# power_management.net
KiCad netlist of a schematic drawn in Altium Designer
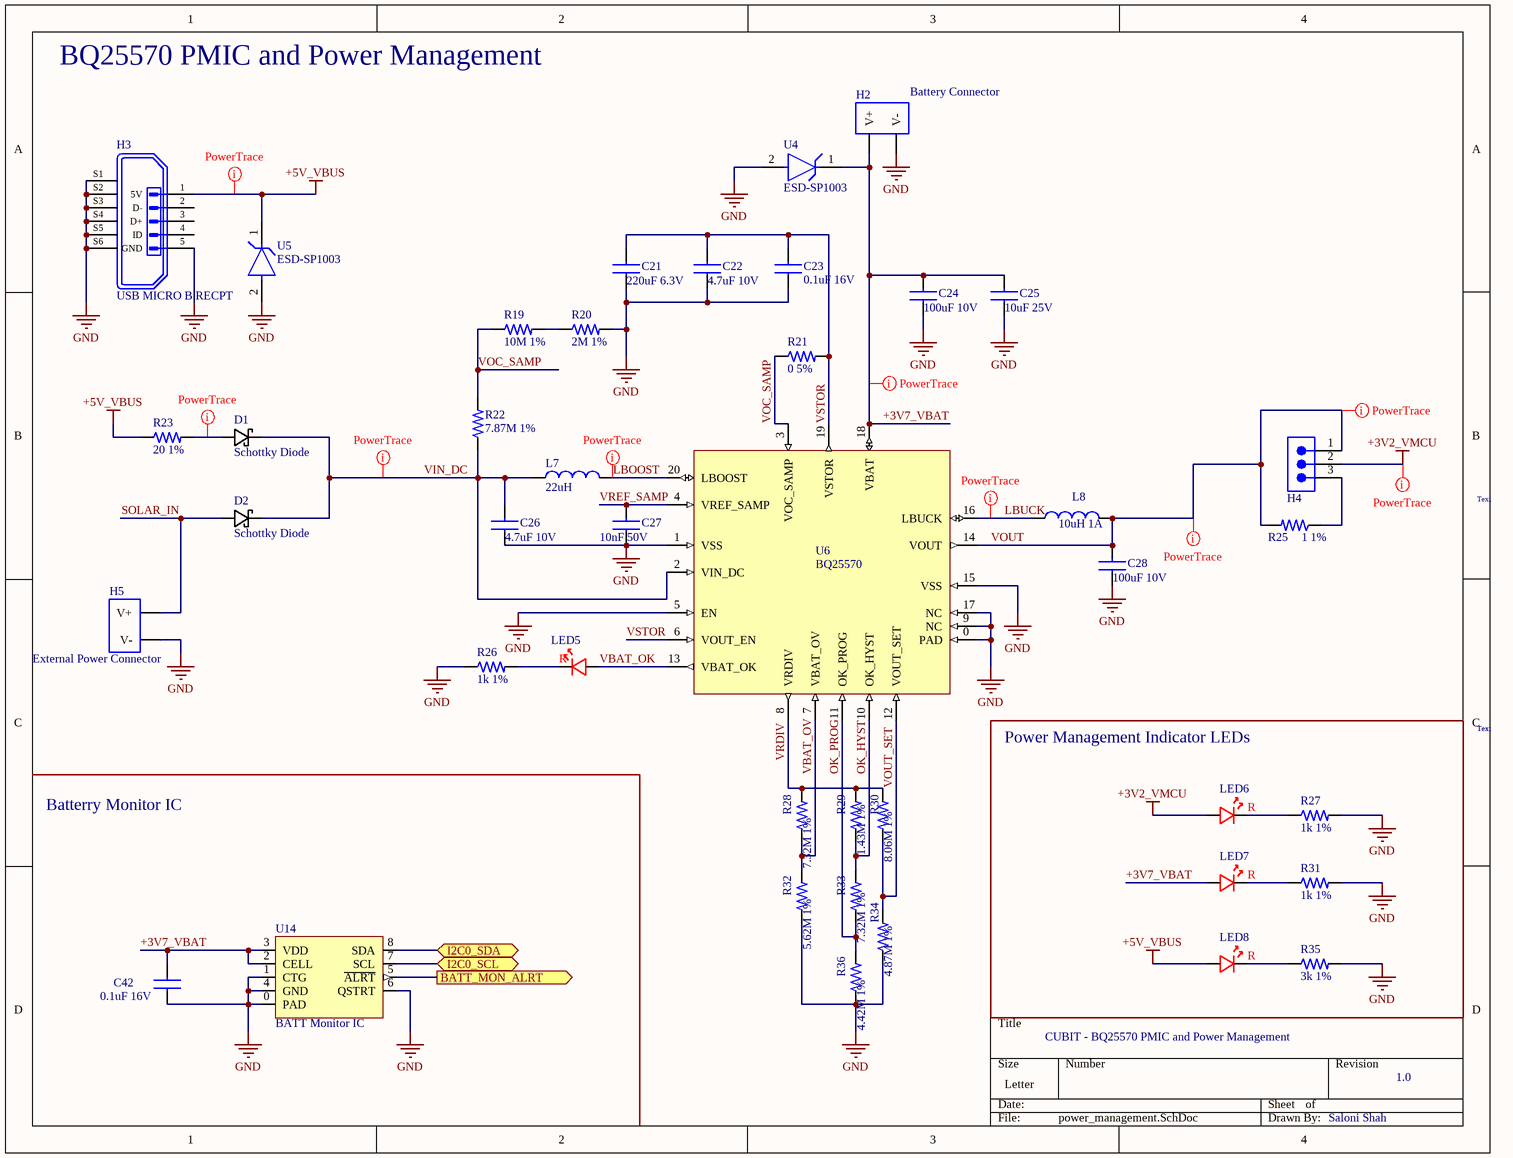
[diagram p0: power_management.SchDoc]

(export (version "E")
  (design (tool "Eeschema 10.0.6"))
  (components
    (comp (ref "C21")
      (value "220uF 6.3V")
      (footprint "Chip_1210_3.2x2.5")
      (description "Cap 220uF 6.3volts X5R 20%")
      (fields
        (field (name "MANUFACTURER") "Murata")
        (field (name "MANUFACTURER PART NUMBER") "GRM32ER60J227ME05L")
      )
      (libsource (lib "LPEDT_proj_lib") (part "GRM32ER60J227ME05L"))
    )
    (comp (ref "C22")
      (value "4.7uF 10V")
      (footprint "CAP_0603_1MM")
      (description "Cap CL10 Series 4.7 uF 10 V ±10 % Tolerance X5R SMT Multilayer Ceramic Capacitor")
      (fields
        (field (name "MANUFACTURER") "Samsung")
        (field (name "MANUFACTURER PART NUMBER") "CL10A475KP8NNNC")
      )
      (libsource (lib "LPEDT_proj_lib") (part "CL10A475KP8NNNC"))
    )
    (comp (ref "C23")
      (value "0.1uF 16V")
      (footprint "CAP_0603_1MM")
      (description "Cap Ceramic 0.1uF 16V X7R 10% SMD 0603 125°C Paper T/R")
      (fields
        (field (name "MANUFACTURER") "KEMET")
        (field (name "MANUFACTURER PART NUMBER") "C0805C104K4RACAUTO")
      )
      (libsource (lib "LPEDT_proj_lib") (part "C0805C104K4RACAUTO"))
    )
    (comp (ref "C24")
      (value "100uF 10V")
      (footprint "Chip_1210_3.2x2.5")
      (description "Cap 100uF ±20% 10V X5R 1210")
      (fields
        (field (name "MANUFACTURER") "Samsung")
        (field (name "MANUFACTURER PART NUMBER") "CL32A107MPVNNNE")
      )
      (libsource (lib "LPEDT_proj_lib") (part "CL32A107MPVNNNE"))
    )
    (comp (ref "C25")
      (value "10uF 25V")
      (footprint "CAP_0805_02X125")
      (description "Cap 0805 25 V 10 uF ±20% Tolerance X5R Monolithic Ceramic Chip Capacitor")
      (fields
        (field (name "MANUFACTURER") "Murata")
        (field (name "MANUFACTURER PART NUMBER") "GRM21BR61E106KA73K")
      )
      (libsource (lib "LPEDT_proj_lib") (part "GRM21BR61E106KA73K"))
    )
    (comp (ref "C26")
      (value "4.7uF 10V")
      (footprint "CAP_0603_1MM")
      (description "Cap CL10 Series 4.7 uF 10 V ±10 % Tolerance X5R SMT Multilayer Ceramic Capacitor")
      (fields
        (field (name "MANUFACTURER") "Samsung")
        (field (name "MANUFACTURER PART NUMBER") "CL10A475KP8NNNC")
      )
      (libsource (lib "LPEDT_proj_lib") (part "CL10A475KP8NNNC"))
    )
    (comp (ref "C27")
      (value "10nF 50V")
      (footprint "CAP_0805_02X125")
      (description "Cap 10nF ±10% 50V X7R 0805")
      (fields
        (field (name "MANUFACTURER") "Samsung")
        (field (name "MANUFACTURER PART NUMBER") "CL21B103KBCNNNC")
      )
      (libsource (lib "LPEDT_proj_lib") (part "CL21B103KBCNNNC"))
    )
    (comp (ref "C28")
      (value "100uF 10V")
      (footprint "Chip_1210_3.2x2.5")
      (description "Cap 100uF ±20% 10V X5R 1210")
      (fields
        (field (name "MANUFACTURER") "Samsung")
        (field (name "MANUFACTURER PART NUMBER") "CL32A107MPVNNNE")
      )
      (libsource (lib "LPEDT_proj_lib") (part "CL32A107MPVNNNE"))
    )
    (comp (ref "C42")
      (value "0.1uF 16V")
      (footprint "CAP_0603_1MM")
      (description "Cap Ceramic 0.1uF 16V X7R 10% SMD 0603 125°C Paper T/R")
      (fields
        (field (name "MANUFACTURER") "KEMET")
        (field (name "MANUFACTURER PART NUMBER") "C0805C104K4RACAUTO")
      )
      (libsource (lib "LPEDT_proj_lib") (part "C0805C104K4RACAUTO"))
    )
    (comp (ref "D1")
      (value "Schottky Diode")
      (footprint "SCHOTTKY4336X33N")
      (description "LSM115J Series 15 V 1 A Surface Mount Schottky Rectifier - DO-214BA")
      (fields
        (field (name "MANUFACTURER") "Microchip")
        (field (name "MANUFACTURER PART NUMBER") "LSM115JE3/TR13")
      )
      (libsource (lib "LPEDT_proj_lib") (part "LSM115JE3/TR13"))
    )
    (comp (ref "D2")
      (value "Schottky Diode")
      (footprint "SCHOTTKY4336X33N")
      (description "LSM115J Series 15 V 1 A Surface Mount Schottky Rectifier - DO-214BA")
      (fields
        (field (name "MANUFACTURER") "Microchip")
        (field (name "MANUFACTURER PART NUMBER") "LSM115JE3/TR13")
      )
      (libsource (lib "LPEDT_proj_lib") (part "LSM115JE3/TR13"))
    )
    (comp (ref "H2")
      (value "Battery Connector")
      (footprint "BAT_CONN")
      (description "2.00mm Pitch Mi ll System Wire-to-Board Header, Surface Mount, Single Row, Vertical, 2 Circuits")
      (fields (field (name "MANUFACTURER") "Molex") (field (name "MANUFACTURER PART NUMBER") "0554600272"))
      (libsource (lib "LPEDT_proj_lib") (part "0554600272"))
    )
    (comp (ref "H3")
      (value "USB MICRO B RECPT")
      (footprint "MICROUSB_AMPHENOL_10118194-0001LF")
      (description "USB - micro B USB 2.0 Receptacle Connector 5 Position Surface Mount, Right Angle; Through Hole")
      (fields
        (field (name "MANUFACTURER") "Amphenol FCI")
        (field (name "MANUFACTURER PART NUMBER") "10118194-0001LF")
      )
      (libsource (lib "LPEDT_proj_lib") (part "10118194-0001LF"))
    )
    (comp (ref "H4")
      (value "PREC003SAAN-RC")
      (footprint "3_PIN_100mil")
      (description "Connector Header Through Hole 3 position 0.100\" (2.54mm)")
      (fields (field (name "DIGIKEY PART") "S1012EC-03-ND") (field (name "LCSC PART#") "C429954"))
      (libsource (lib "LPEDT_proj_lib") (part "SW_3Pin_100mil_Switch"))
    )
    (comp (ref "H5")
      (value "External Power Connector")
      (footprint "2_PIN_100mil")
      (libsource (lib "LPEDT_proj_lib") (part "ext_pwr_conn"))
    )
    (comp (ref "L7")
      (value "22uH")
      (footprint "2_IND_3x3")
      (description "Inductor Power Shielded Wirewound 22uH 20% 1MHz Ferrite 0.87A 0.496Ohm DCR 1212 T/R")
      (fields
        (field (name "MANUFACTURER") "TDK")
        (field (name "MANUFACTURER PART NUMBER") "VLS3015CX-220M-1")
      )
      (libsource (lib "LPEDT_proj_lib") (part "VLS3015CX-220M-1"))
    )
    (comp (ref "L8")
      (value "10uH 1A")
      (footprint "2_chip_2.5x2")
      (description "Inductor Power Shielded Multi-Layer 10uH 20% 1MHz Metal 0.85A 0.46Ohm DCR 1008 T/R")
      (fields
        (field (name "MANUFACTURER") "Murata")
        (field (name "MANUFACTURER PART NUMBER") "1239AS-H-100M=P2")
      )
      (libsource (lib "LPEDT_proj_lib") (part "1239AS-H-100M=P2"))
    )
    (comp (ref "LED5")
      (value "150060RS75000")
      (footprint "LED_0603_RED_WL-SMCW")
      (description "LED Low-Power Uni-Color Red 630nm 2V 2-Pin Chip 0603(1608Metric) T/R")
      (fields (field (name "MANUFACTURER") "Wurth Electronics"))
      (libsource (lib "LPEDT_proj_lib") (part "150060RS75000"))
    )
    (comp (ref "LED6")
      (value "150060RS75000")
      (footprint "LED_0603_RED_WL-SMCW")
      (description "LED Low-Power Uni-Color Red 630nm 2V 2-Pin Chip 0603(1608Metric) T/R")
      (fields (field (name "MANUFACTURER") "Wurth Electronics"))
      (libsource (lib "LPEDT_proj_lib") (part "150060RS75000"))
    )
    (comp (ref "LED7")
      (value "150060RS75000")
      (footprint "LED_0603_RED_WL-SMCW")
      (description "LED Low-Power Uni-Color Red 630nm 2V 2-Pin Chip 0603(1608Metric) T/R")
      (fields (field (name "MANUFACTURER") "Wurth Electronics"))
      (libsource (lib "LPEDT_proj_lib") (part "150060RS75000"))
    )
    (comp (ref "LED8")
      (value "150060RS75000")
      (footprint "LED_0603_RED_WL-SMCW")
      (description "LED Low-Power Uni-Color Red 630nm 2V 2-Pin Chip 0603(1608Metric) T/R")
      (fields (field (name "MANUFACTURER") "Wurth Electronics"))
      (libsource (lib "LPEDT_proj_lib") (part "150060RS75000"))
    )
    (comp (ref "R19")
      (value "10M 1%")
      (footprint "2_Chip_0603_RMCF")
      (description "Res 10M Ohm 1% 1/10W ±200ppm/°C Molded SMD SMD Paper T/R")
      (fields
        (field (name "MANUFACTURER") "Stackpole Electronics")
        (field (name "MANUFACTURER PART NUMBER") "RMCF0603FT10M0")
      )
      (libsource (lib "LPEDT_proj_lib") (part "RMCF0603FT10M0"))
    )
    (comp (ref "R20")
      (value "2M 1%")
      (footprint "2_Chip_0603_RMCF")
      (description "RES 2M OHM 1% 1/10W 0603")
      (fields
        (field (name "MANUFACTURER") "Stackpole Electronics")
        (field (name "MANUFACTURER PART NUMBER") "RMCF0603FT2M00")
      )
      (libsource (lib "LPEDT_proj_lib") (part "RMCF0603FT2M00"))
    )
    (comp (ref "R21")
      (value "0 5%")
      (footprint "CAP_0402_1mm")
      (description "Res 0 Ohms ±5% 0.063 W 0402 Thick Film Surface Mount Chip Resistor")
      (fields
        (field (name "MANUFACTURER") "Samsung")
        (field (name "MANUFACTURER PART NUMBER") "RC1005J000CS")
      )
      (libsource (lib "LPEDT_proj_lib") (part "RC1005J000CS"))
    )
    (comp (ref "R22")
      (value "7.87M 1%")
      (footprint "2_Chip_0603_RMCF")
      (description "Res 7.87M Ohm 1% 1/10W ±200ppm/°C Molded SMD SMD Paper T/R")
      (fields
        (field (name "MANUFACTURER") "Stackpole Electronics")
        (field (name "MANUFACTURER PART NUMBER") "RMCF0603FT7M87")
      )
      (libsource (lib "LPEDT_proj_lib") (part "RMCF0603FT7M87"))
    )
    (comp (ref "R23")
      (value "20 1%")
      (footprint "2_Chip_0603_RMCF")
      (description "Res High Voltage 0603 20 Ohm 1/10W 1% SMD")
      (fields (field (name "MANUFACTURER") "Rohm") (field (name "MANUFACTURER PART NUMBER") "KTR03EZPF20R0"))
      (libsource (lib "LPEDT_proj_lib") (part "KTR03EZPF20R0"))
    )
    (comp (ref "R25")
      (value "1 1%")
      (footprint "CAP_0603_1MM")
      (description "Res 1 Ohm 1% 1/10W ±200ppm/°C Molded SMD SMD Paper T/R")
      (fields
        (field (name "MANUFACTURER") "Yageo")
        (field (name "MANUFACTURER PART NUMBER") "RC0603FR-101RL")
      )
      (libsource (lib "LPEDT_proj_lib") (part "RC0603FR-101RL"))
    )
    (comp (ref "R26")
      (value "1k 1%")
      (footprint "2_Chip_0603_RMCF")
      (description "Res 1K Ohm 1% 0.1W(1/10W) ±100ppm/C Pad SMD Automotive T/R")
      (fields
        (field (name "MANUFACTURER") "Stackpole Electronics")
        (field (name "MANUFACTURER PART NUMBER") "RMCF0603FT1K00")
      )
      (libsource (lib "LPEDT_proj_lib") (part "RMCF0603FT1K00"))
    )
    (comp (ref "R27")
      (value "1k 1%")
      (footprint "2_Chip_0603_RMCF")
      (description "Res 1K Ohm 1% 0.1W(1/10W) ±100ppm/C Pad SMD Automotive T/R")
      (fields
        (field (name "MANUFACTURER") "Stackpole Electronics")
        (field (name "MANUFACTURER PART NUMBER") "RMCF0603FT1K00")
      )
      (libsource (lib "LPEDT_proj_lib") (part "RMCF0603FT1K00"))
    )
    (comp (ref "R28")
      (value "7.32M 1%")
      (footprint "2_Chip_0603_RMCF")
      (description "Res 7.32M Ohm 1% 1/10W ±200ppm/°C Molded SMD SMD Paper T/R")
      (fields
        (field (name "MANUFACTURER") "Stackpole Electronics")
        (field (name "MANUFACTURER PART NUMBER") "RMCF0603FT7M32")
      )
      (libsource (lib "LPEDT_proj_lib") (part "RMCF0603FT7M32"))
    )
    (comp (ref "R29")
      (value "1.43M 1%")
      (footprint "2_Chip_0603_RMCF")
      (description "Res 1.43M Ohm 1% 1/10W ±200ppm/°C Molded SMD SMD Paper T/R")
      (fields
        (field (name "MANUFACTURER") "Stackpole Electronics")
        (field (name "MANUFACTURER PART NUMBER") "RMCF0603FT1M43")
      )
      (libsource (lib "LPEDT_proj_lib") (part "RMCF0603FT1M43"))
    )
    (comp (ref "R30")
      (value "8.06M 1%")
      (footprint "2_Chip_0603_RMCF")
      (description "Res 8.06M Ohm 1% 1/10W ±200ppm/°C Molded SMD SMD Paper T/R")
      (fields
        (field (name "MANUFACTURER") "Stackpole Electronics")
        (field (name "MANUFACTURER PART NUMBER") "RMCF0603FT8M06")
      )
      (libsource (lib "LPEDT_proj_lib") (part "RMCF0603FT8M06"))
    )
    (comp (ref "R31")
      (value "1k 1%")
      (footprint "2_Chip_0603_RMCF")
      (description "Res 1K Ohm 1% 0.1W(1/10W) ±100ppm/C Pad SMD Automotive T/R")
      (fields
        (field (name "MANUFACTURER") "Stackpole Electronics")
        (field (name "MANUFACTURER PART NUMBER") "RMCF0603FT1K00")
      )
      (libsource (lib "LPEDT_proj_lib") (part "RMCF0603FT1K00"))
    )
    (comp (ref "R32")
      (value "5.62M 1%")
      (footprint "2_Chip_0603_RMCF")
      (description "Res 5.62M Ohm 1% 1/10W ±200ppm/°C Molded SMD SMD Paper T/R")
      (fields
        (field (name "MANUFACTURER") "Stackpole Electronics")
        (field (name "MANUFACTURER PART NUMBER") "RMCF0603FT5M62")
      )
      (libsource (lib "LPEDT_proj_lib") (part "RMCF0603FT5M62"))
    )
    (comp (ref "R33")
      (value "7.32M 1%")
      (footprint "2_Chip_0603_RMCF")
      (description "Res 7.32M Ohm 1% 1/10W ±200ppm/°C Molded SMD SMD Paper T/R")
      (fields
        (field (name "MANUFACTURER") "Stackpole Electronics")
        (field (name "MANUFACTURER PART NUMBER") "RMCF0603FT7M32")
      )
      (libsource (lib "LPEDT_proj_lib") (part "RMCF0603FT7M32"))
    )
    (comp (ref "R34")
      (value "4.87M 1%")
      (footprint "2_Chip_0603_RMCF")
      (description "Res 4.87M Ohm 1% 1/10W ±200ppm/°C Molded SMD SMD Paper T/R")
      (fields
        (field (name "MANUFACTURER") "Stackpole Electronics")
        (field (name "MANUFACTURER PART NUMBER") "RMCF0603FT4M87")
      )
      (libsource (lib "LPEDT_proj_lib") (part "RMCF0603FT4M87"))
    )
    (comp (ref "R35")
      (value "3k 1%")
      (footprint "CAP_0603_1MM")
      (description "Res 3000Ω ± 1.00% 0.1W ± 100ppm/℃ 0603")
      (fields
        (field (name "MANUFACTURER") "Yageo")
        (field (name "MANUFACTURER PART NUMBER") "RC0603FR-073KL")
      )
      (libsource (lib "LPEDT_proj_lib") (part "RC0603FR-073KL"))
    )
    (comp (ref "R36")
      (value "4.42M 1%")
      (footprint "2_Chip_0603_RMCF")
      (description "Res 4.42M Ohm 1% 1/10W ±200ppm/°C Molded SMD SMD Paper T/R")
      (fields
        (field (name "MANUFACTURER") "Stackpole Electronics")
        (field (name "MANUFACTURER PART NUMBER") "RMCF0603FT4M42")
      )
      (libsource (lib "LPEDT_proj_lib") (part "RMCF0603FT4M42"))
    )
    (comp (ref "U4")
      (value "ESD-SP1003")
      (footprint "Littelfuse_Inc_SP1003_MFG")
      (description "TVS DIODE 5VWM 12VC SOD723")
      (fields
        (field (name "MANUFACTURER") "Littelfuse")
        (field (name "MANUFACTURER PART NUMBER") "SP1003-01DTG")
      )
      (libsource (lib "LPEDT_proj_lib") (part "SP1003-01DTG"))
    )
    (comp (ref "U5")
      (value "ESD-SP1003")
      (footprint "Littelfuse_Inc_SP1003_MFG")
      (description "TVS DIODE 5VWM 12VC SOD723")
      (fields
        (field (name "MANUFACTURER") "Littelfuse")
        (field (name "MANUFACTURER PART NUMBER") "SP1003-01DTG")
      )
      (libsource (lib "LPEDT_proj_lib") (part "SP1003-01DTG"))
    )
    (comp (ref "U6")
      (value "BQ25570")
      (footprint "21_QFN_35x35")
      (description "Switching Battery Charger Li-Ion/Li-Pol/Supercapacitor 110mA 2.2V to 5.5V 20-Pin VQFN EP T/R")
      (fields
        (field (name "MANUFACTURER") "Texas Instruments")
        (field (name "MANUFACTURER PART NUMBER") "BQ25570RGRT")
      )
      (libsource (lib "LPEDT_proj_lib") (part "BQ25570RGRT"))
    )
    (comp (ref "U14")
      (value "BATT Monitor IC")
      (footprint "MAX17048")
      (description "Battery Battery Monitor IC Lithium-Ion 8-TDFN-EP (")
      (fields (field (name "MANUFACTURER") "Maxim") (field (name "MANUFACTURER PART NUMBER") "MAX17048G+T10"))
      (libsource (lib "LPEDT_proj_lib") (part "MAX17048G+T10"))
    )
  )
  (nets
    (net (code "1") (name "+3V2_VMCU") (class "Default")
      (node (ref "H4") (pin "2") (pinfunction "2_2") (pintype "passive"))
      (node (ref "LED6") (pin "A") (pinfunction "A_A") (pintype "passive"))
    )
    (net (code "2") (name "+5V_VBUS") (class "Default")
      (node (ref "H3") (pin "1") (pinfunction "5V_1") (pintype "power_in"))
      (node (ref "LED8") (pin "A") (pinfunction "A_A") (pintype "passive"))
      (node (ref "R23") (pin "1") (pinfunction "1_1") (pintype "passive"))
      (node (ref "U5") (pin "1") (pinfunction "C_1") (pintype "passive"))
    )
    (net (code "3") (name "/+3V7_VBAT") (class "Default")
      (node (ref "C24") (pin "1") (pinfunction "1_1") (pintype "passive"))
      (node (ref "C25") (pin "1") (pinfunction "1_1") (pintype "passive"))
      (node (ref "C42") (pin "1") (pinfunction "1_1") (pintype "passive"))
      (node (ref "H2") (pin "V+") (pinfunction "V+_V+") (pintype "passive"))
      (node (ref "LED7") (pin "A") (pinfunction "A_A") (pintype "passive"))
      (node (ref "U14") (pin "2") (pinfunction "CELL_2") (pintype "power_in"))
      (node (ref "U14") (pin "3") (pinfunction "VDD_3") (pintype "power_in"))
      (node (ref "U4") (pin "1") (pinfunction "C_1") (pintype "passive"))
      (node (ref "U6") (pin "18") (pinfunction "VBAT_18") (pintype "bidirectional"))
    )
    (net (code "4") (name "/BATT_MON_ALRT") (class "Default")
      (node (ref "U14") (pin "5") (pinfunction "~{ALRT}_5") (pintype "output"))
    )
    (net (code "5") (name "/I2C0_SCL") (class "Default")
      (node (ref "U14") (pin "7") (pinfunction "SCL_7") (pintype "passive"))
    )
    (net (code "6") (name "/I2C0_SDA") (class "Default")
      (node (ref "U14") (pin "8") (pinfunction "SDA_8") (pintype "passive"))
    )
    (net (code "7") (name "/LBOOST") (class "Default")
      (node (ref "L7") (pin "2") (pinfunction "2_2") (pintype "passive"))
      (node (ref "U6") (pin "20") (pinfunction "LBOOST_20") (pintype "bidirectional"))
    )
    (net (code "8") (name "/LBUCK") (class "Default")
      (node (ref "L8") (pin "1") (pinfunction "1_1") (pintype "passive"))
      (node (ref "U6") (pin "16") (pinfunction "LBUCK_16") (pintype "bidirectional"))
    )
    (net (code "9") (name "/OK_HYST") (class "Default")
      (node (ref "R29") (pin "1") (pinfunction "1_1") (pintype "passive"))
      (node (ref "R33") (pin "2") (pinfunction "2_2") (pintype "passive"))
      (node (ref "U6") (pin "10") (pinfunction "OK_HYST_10") (pintype "input"))
    )
    (net (code "10") (name "/OK_PROG") (class "Default")
      (node (ref "R33") (pin "1") (pinfunction "1_1") (pintype "passive"))
      (node (ref "R36") (pin "2") (pinfunction "2_2") (pintype "passive"))
      (node (ref "U6") (pin "11") (pinfunction "OK_PROG_11") (pintype "input"))
    )
    (net (code "11") (name "/SOLAR_IN") (class "Default")
      (node (ref "D2") (pin "A") (pinfunction "A_A") (pintype "passive"))
      (node (ref "H5") (pin "1") (pinfunction "V+_1") (pintype "passive"))
    )
    (net (code "12") (name "/VBAT_OK") (class "Default")
      (node (ref "LED5") (pin "A") (pinfunction "A_A") (pintype "passive"))
      (node (ref "U6") (pin "13") (pinfunction "VBAT_OK_13") (pintype "output"))
    )
    (net (code "13") (name "/VBAT_OV") (class "Default")
      (node (ref "R28") (pin "1") (pinfunction "1_1") (pintype "passive"))
      (node (ref "R32") (pin "2") (pinfunction "2_2") (pintype "passive"))
      (node (ref "U6") (pin "7") (pinfunction "VBAT_OV_7") (pintype "input"))
    )
    (net (code "14") (name "/VIN_DC") (class "Default")
      (node (ref "C26") (pin "1") (pinfunction "1_1") (pintype "passive"))
      (node (ref "D1") (pin "C") (pinfunction "C_C") (pintype "passive"))
      (node (ref "D2") (pin "C") (pinfunction "C_C") (pintype "passive"))
      (node (ref "L7") (pin "1") (pinfunction "1_1") (pintype "passive"))
      (node (ref "R22") (pin "1") (pinfunction "1_1") (pintype "passive"))
      (node (ref "U6") (pin "2") (pinfunction "VIN_DC_2") (pintype "input"))
    )
    (net (code "15") (name "/VOC_SAMP") (class "Default")
      (node (ref "R19") (pin "1") (pinfunction "1_1") (pintype "passive"))
      (node (ref "R21") (pin "1") (pinfunction "1_1") (pintype "passive"))
      (node (ref "R22") (pin "2") (pinfunction "2_2") (pintype "passive"))
      (node (ref "U6") (pin "3") (pinfunction "VOC_SAMP_3") (pintype "input"))
    )
    (net (code "16") (name "/VOUT") (class "Default")
      (node (ref "C28") (pin "1") (pinfunction "1_1") (pintype "passive"))
      (node (ref "H4") (pin "1") (pinfunction "1_1") (pintype "passive"))
      (node (ref "L8") (pin "2") (pinfunction "2_2") (pintype "passive"))
      (node (ref "R25") (pin "2") (pinfunction "2_2") (pintype "passive"))
      (node (ref "U6") (pin "14") (pinfunction "VOUT_14") (pintype "output"))
    )
    (net (code "17") (name "/VOUT_SET") (class "Default")
      (node (ref "R30") (pin "1") (pinfunction "1_1") (pintype "passive"))
      (node (ref "R34") (pin "2") (pinfunction "2_2") (pintype "passive"))
      (node (ref "U6") (pin "12") (pinfunction "VOUT_SET_12") (pintype "input"))
    )
    (net (code "18") (name "/VRDIV") (class "Default")
      (node (ref "R28") (pin "2") (pinfunction "2_2") (pintype "passive"))
      (node (ref "R29") (pin "2") (pinfunction "2_2") (pintype "passive"))
      (node (ref "R30") (pin "2") (pinfunction "2_2") (pintype "passive"))
      (node (ref "U6") (pin "8") (pinfunction "VRDIV_8") (pintype "output"))
    )
    (net (code "19") (name "/VREF_SAMP") (class "Default")
      (node (ref "C27") (pin "1") (pinfunction "1_1") (pintype "passive"))
      (node (ref "U6") (pin "4") (pinfunction "VREF_SAMP_4") (pintype "input"))
    )
    (net (code "20") (name "/VSTOR") (class "Default")
      (node (ref "C21") (pin "1") (pinfunction "1_1") (pintype "passive"))
      (node (ref "C22") (pin "1") (pinfunction "1_1") (pintype "passive"))
      (node (ref "C23") (pin "1") (pinfunction "1_1") (pintype "passive"))
      (node (ref "R21") (pin "2") (pinfunction "2_2") (pintype "passive"))
      (node (ref "U6") (pin "19") (pinfunction "VSTOR_19") (pintype "output"))
      (node (ref "U6") (pin "6") (pinfunction "VOUT_EN_6") (pintype "input"))
    )
    (net (code "21") (name "GND") (class "Default")
      (node (ref "C21") (pin "2") (pinfunction "2_2") (pintype "passive"))
      (node (ref "C22") (pin "2") (pinfunction "2_2") (pintype "passive"))
      (node (ref "C23") (pin "2") (pinfunction "2_2") (pintype "passive"))
      (node (ref "C24") (pin "2") (pinfunction "2_2") (pintype "passive"))
      (node (ref "C25") (pin "2") (pinfunction "2_2") (pintype "passive"))
      (node (ref "C26") (pin "2") (pinfunction "2_2") (pintype "passive"))
      (node (ref "C27") (pin "2") (pinfunction "2_2") (pintype "passive"))
      (node (ref "C28") (pin "2") (pinfunction "2_2") (pintype "passive"))
      (node (ref "C42") (pin "2") (pinfunction "2_2") (pintype "passive"))
      (node (ref "H2") (pin "V-") (pinfunction "V-_V-") (pintype "passive"))
      (node (ref "H3") (pin "5") (pinfunction "GND_5") (pintype "passive"))
      (node (ref "H3") (pin "S1") (pinfunction "S1_S1") (pintype "passive"))
      (node (ref "H3") (pin "S2") (pinfunction "S2_S2") (pintype "passive"))
      (node (ref "H3") (pin "S3") (pinfunction "S3_S3") (pintype "passive"))
      (node (ref "H3") (pin "S4") (pinfunction "S4_S4") (pintype "passive"))
      (node (ref "H3") (pin "S5") (pinfunction "S5_S5") (pintype "passive"))
      (node (ref "H3") (pin "S6") (pinfunction "S6_S6") (pintype "passive"))
      (node (ref "H5") (pin "2") (pinfunction "V-_2") (pintype "passive"))
      (node (ref "R20") (pin "2") (pinfunction "2_2") (pintype "passive"))
      (node (ref "R26") (pin "1") (pinfunction "1_1") (pintype "passive"))
      (node (ref "R27") (pin "2") (pinfunction "2_2") (pintype "passive"))
      (node (ref "R31") (pin "2") (pinfunction "2_2") (pintype "passive"))
      (node (ref "R32") (pin "1") (pinfunction "1_1") (pintype "passive"))
      (node (ref "R34") (pin "1") (pinfunction "1_1") (pintype "passive"))
      (node (ref "R35") (pin "2") (pinfunction "2_2") (pintype "passive"))
      (node (ref "R36") (pin "1") (pinfunction "1_1") (pintype "passive"))
      (node (ref "U14") (pin "0") (pinfunction "PAD_0") (pintype "power_in"))
      (node (ref "U14") (pin "1") (pinfunction "CTG_1") (pintype "power_in"))
      (node (ref "U14") (pin "4") (pinfunction "GND_4") (pintype "power_in"))
      (node (ref "U14") (pin "6") (pinfunction "QSTRT_6") (pintype "passive"))
      (node (ref "U4") (pin "2") (pinfunction "A_2") (pintype "passive"))
      (node (ref "U5") (pin "2") (pinfunction "A_2") (pintype "passive"))
      (node (ref "U6") (pin "0") (pinfunction "PAD_0") (pintype "input"))
      (node (ref "U6") (pin "1") (pinfunction "VSS_1") (pintype "input"))
      (node (ref "U6") (pin "15") (pinfunction "VSS_15") (pintype "input"))
      (node (ref "U6") (pin "17") (pinfunction "NC_17") (pintype "input"))
      (node (ref "U6") (pin "5") (pinfunction "EN_5") (pintype "input"))
      (node (ref "U6") (pin "9") (pinfunction "NC_9") (pintype "input"))
    )
    (net (code "22") (name "Net-(D1-PadA)") (class "Default")
      (node (ref "D1") (pin "A") (pinfunction "A_A") (pintype "passive"))
      (node (ref "R23") (pin "2") (pinfunction "2_2") (pintype "passive"))
    )
    (net (code "23") (name "Net-(H4-Pad3)") (class "Default")
      (node (ref "H4") (pin "3") (pinfunction "3_3") (pintype "passive"))
      (node (ref "R25") (pin "1") (pinfunction "1_1") (pintype "passive"))
    )
    (net (code "24") (name "Net-(LED5-PadC)") (class "Default")
      (node (ref "LED5") (pin "C") (pinfunction "C_C") (pintype "passive"))
      (node (ref "R26") (pin "2") (pinfunction "2_2") (pintype "passive"))
    )
    (net (code "25") (name "Net-(LED6-PadC)") (class "Default")
      (node (ref "LED6") (pin "C") (pinfunction "C_C") (pintype "passive"))
      (node (ref "R27") (pin "1") (pinfunction "1_1") (pintype "passive"))
    )
    (net (code "26") (name "Net-(LED7-PadC)") (class "Default")
      (node (ref "LED7") (pin "C") (pinfunction "C_C") (pintype "passive"))
      (node (ref "R31") (pin "1") (pinfunction "1_1") (pintype "passive"))
    )
    (net (code "27") (name "Net-(LED8-PadC)") (class "Default")
      (node (ref "LED8") (pin "C") (pinfunction "C_C") (pintype "passive"))
      (node (ref "R35") (pin "1") (pinfunction "1_1") (pintype "passive"))
    )
    (net (code "28") (name "Net-(R19-Pad2)") (class "Default")
      (node (ref "R19") (pin "2") (pinfunction "2_2") (pintype "passive"))
      (node (ref "R20") (pin "1") (pinfunction "1_1") (pintype "passive"))
    )
    (net (code "29") (name "unconnected-(H3-D+-Pad3)") (class "Default")
      (node (ref "H3") (pin "3") (pinfunction "D+_3") (pintype "passive"))
    )
    (net (code "30") (name "unconnected-(H3-D--Pad2)") (class "Default")
      (node (ref "H3") (pin "2") (pinfunction "D-_2") (pintype "passive"))
    )
    (net (code "31") (name "unconnected-(H3-ID-Pad4)") (class "Default")
      (node (ref "H3") (pin "4") (pinfunction "ID_4") (pintype "passive"))
    )
  )
)
